# PMP20873E1_Control.net
KiCad netlist of a schematic drawn in Altium Designer
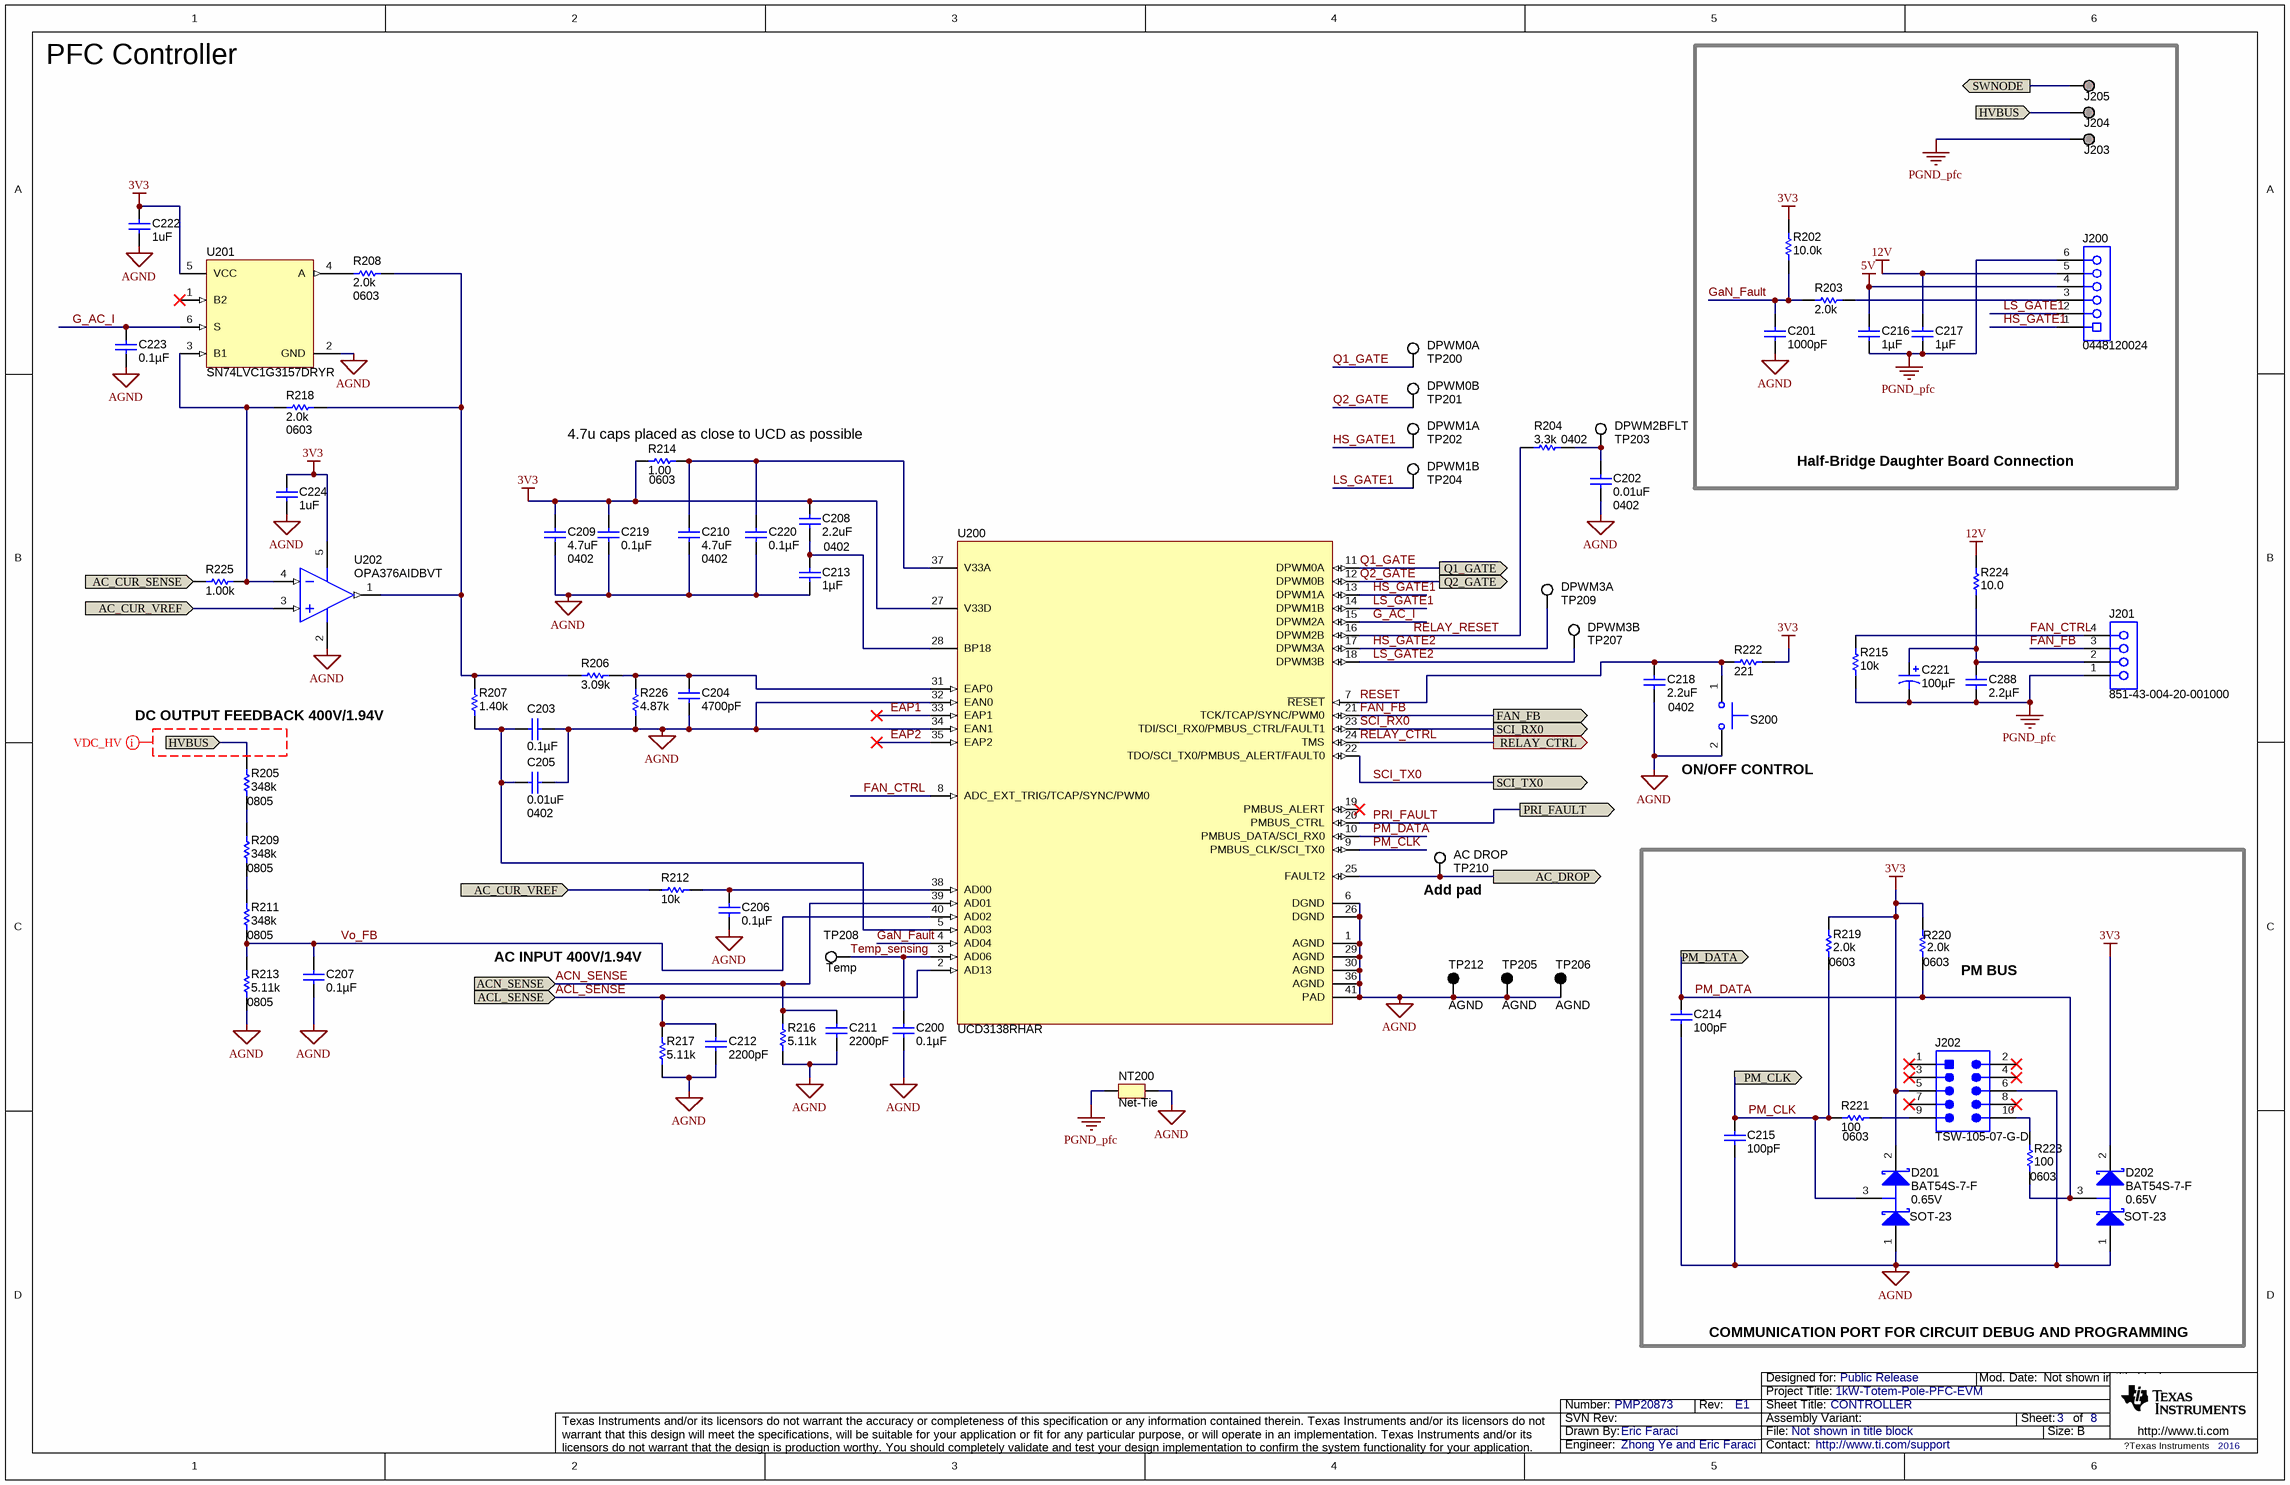
[diagram p0: PMP20873E1_Control.SchDoc]

(export (version "E")
  (design (tool "Eeschema 10.0.6"))
  (components
    (comp (ref "C200")
      (value "GRM155R60J104KA01D")
      (footprint "0402")
      (description "CAP, CERM, 0.1uF, 6.3V, +/-10%, X5R, 0402")
      (fields
        (field (name "VALUEDISPLAYED") "0.1µF")
        (field (name "MANUFACTURER") "MuRata")
        (field (name "PUBLISHER") "Texas Instruments")
      )
      (libsource (lib "Capacitor_Ceramic") (part "GRM155R60J104KA01D"))
    )
    (comp (ref "C201")
      (value "GRM155R61A102KA01D")
      (footprint "0402")
      (description "CAP, CERM, 1000pF, 10V, +/-10%, X5R, 0402")
      (fields
        (field (name "VALUEDISPLAYED") "1000pF")
        (field (name "MANUFACTURER") "MuRata")
        (field (name "PUBLISHER") "Texas Instruments")
      )
      (libsource (lib "Capacitor_Ceramic") (part "GRM155R61A102KA01D"))
    )
    (comp (ref "C202")
      (value "GRM155R70J103KA01D")
      (footprint "0402")
      (description "CAP, CERM, 0.01uF, 6.3V, +/-10%, X7R, 0402")
      (fields
        (field (name "VALUEDISPLAYED") "0.01uF")
        (field (name "MANUFACTURER") "MuRata")
        (field (name "PACKAGEREFERENCE") "0402")
        (field (name "PUBLISHER") "Texas Instruments")
      )
      (libsource (lib "Capacitor_Ceramic") (part "GRM155R70J103KA01D"))
    )
    (comp (ref "C203")
      (value "GRM155R60J104KA01D")
      (footprint "0402")
      (description "CAP, CERM, 0.1uF, 6.3V, +/-10%, X5R, 0402")
      (fields
        (field (name "VALUEDISPLAYED") "0.1µF")
        (field (name "MANUFACTURER") "MuRata")
        (field (name "PUBLISHER") "Texas Instruments")
      )
      (libsource (lib "Capacitor_Ceramic") (part "GRM155R60J104KA01D"))
    )
    (comp (ref "C204")
      (value "GRM155R60J472KA01D")
      (footprint "0402")
      (description "CAP, CERM, 4700pF, 6.3V, +/-10%, X5R, 0402")
      (fields
        (field (name "VALUEDISPLAYED") "4700pF")
        (field (name "MANUFACTURER") "MuRata")
        (field (name "PUBLISHER") "Texas Instruments")
      )
      (libsource (lib "Capacitor_Ceramic") (part "GRM155R60J472KA01D"))
    )
    (comp (ref "C205")
      (value "GRM155R70J103KA01D")
      (footprint "0402")
      (description "CAP, CERM, 0.01uF, 6.3V, +/-10%, X7R, 0402")
      (fields
        (field (name "VALUEDISPLAYED") "0.01uF")
        (field (name "MANUFACTURER") "MuRata")
        (field (name "PACKAGEREFERENCE") "0402")
        (field (name "PUBLISHER") "Texas Instruments")
      )
      (libsource (lib "Capacitor_Ceramic") (part "GRM155R70J103KA01D"))
    )
    (comp (ref "C206")
      (value "GRM155R60J104KA01D")
      (footprint "0402")
      (description "CAP, CERM, 0.1uF, 6.3V, +/-10%, X5R, 0402")
      (fields
        (field (name "VALUEDISPLAYED") "0.1µF")
        (field (name "MANUFACTURER") "MuRata")
        (field (name "PUBLISHER") "Texas Instruments")
      )
      (libsource (lib "Capacitor_Ceramic") (part "GRM155R60J104KA01D"))
    )
    (comp (ref "C207")
      (value "GCM188R71H104KA57D")
      (footprint "0603")
      (description "CAP, CERM, 0.1 µF, 50 V, +/- 10%, X7R, 0603")
      (fields
        (field (name "VALUEDISPLAYED") "0.1µF")
        (field (name "MANUFACTURER") "MuRata")
        (field (name "PUBLISHER") "Texas Instruments")
      )
      (libsource (lib "Capacitor_Ceramic") (part "GCM188R71H104KA57D"))
    )
    (comp (ref "C208")
      (value "C1005X5R1A225K050BC")
      (footprint "0402")
      (description "CAP, CERM, 2.2uF, 10V, +/-10%, X5R, 0402")
      (fields
        (field (name "VALUEDISPLAYED") "2.2uF")
        (field (name "MANUFACTURER") "TDK")
        (field (name "PACKAGEREFERENCE") "0402")
        (field (name "PUBLISHER") "Texas Instruments")
      )
      (libsource (lib "Capacitor_Ceramic") (part "C1005X5R1A225K050BC"))
    )
    (comp (ref "C209")
      (value "4.7uF")
      (footprint "0402")
      (description "CAP, CER, 4.7UF, 6.3V, 20%, X5R, 0402")
      (fields
        (field (name "PACKAGEREFERENCE") "0402")
        (field (name "MANUFACTURER") "Samsung Electro-Mechanics America")
        (field (name "PARTNUMBER") "CL05A475MQ5NRNC")
        (field (name "PUBLISHER") "Texas Instruments")
      )
      (libsource (lib "MiscParts") (part "Capacitor"))
    )
    (comp (ref "C210")
      (value "4.7uF")
      (footprint "0402")
      (description "CAP, CER, 4.7UF, 6.3V, 20%, X5R, 0402")
      (fields
        (field (name "PACKAGEREFERENCE") "0402")
        (field (name "MANUFACTURER") "Samsung Electro-Mechanics America")
        (field (name "PARTNUMBER") "CL05A475MQ5NRNC")
        (field (name "PUBLISHER") "Texas Instruments")
      )
      (libsource (lib "MiscParts") (part "Capacitor"))
    )
    (comp (ref "C211")
      (value "C1608X7R1H222K")
      (footprint "0603")
      (description "CAP, CERM, 2200 pF, 50 V, +/- 10%, X7R, 0603")
      (fields
        (field (name "VALUEDISPLAYED") "2200pF")
        (field (name "MANUFACTURER") "TDK")
        (field (name "PUBLISHER") "Texas Instruments")
      )
      (libsource (lib "Capacitor_Ceramic") (part "C1608X7R1H222K"))
    )
    (comp (ref "C212")
      (value "C1608X7R1H222K")
      (footprint "0603")
      (description "CAP, CERM, 2200 pF, 50 V, +/- 10%, X7R, 0603")
      (fields
        (field (name "VALUEDISPLAYED") "2200pF")
        (field (name "MANUFACTURER") "TDK")
        (field (name "PUBLISHER") "Texas Instruments")
      )
      (libsource (lib "Capacitor_Ceramic") (part "C1608X7R1H222K"))
    )
    (comp (ref "C213")
      (value "GRM155R61A105KE15D")
      (footprint "0402")
      (description "CAP, CERM, 1uF, 10V, +/-10%, X5R, 0402")
      (fields
        (field (name "VALUEDISPLAYED") "1µF")
        (field (name "MANUFACTURER") "MuRata")
        (field (name "PUBLISHER") "Texas Instruments")
      )
      (libsource (lib "Capacitor_Ceramic") (part "GRM155R61A105KE15D"))
    )
    (comp (ref "C214")
      (value "GRM1555C1H101JA01D")
      (footprint "0402")
      (description "CAP, CERM, 100pF, 50V, +/-5%, C0G/NP0, 0402")
      (fields
        (field (name "VALUEDISPLAYED") "100pF")
        (field (name "MANUFACTURER") "MuRata")
        (field (name "PUBLISHER") "Texas Instruments")
      )
      (libsource (lib "Capacitor_Ceramic") (part "GRM1555C1H101JA01D"))
    )
    (comp (ref "C215")
      (value "GRM1555C1H101JA01D")
      (footprint "0402")
      (description "CAP, CERM, 100pF, 50V, +/-5%, C0G/NP0, 0402")
      (fields
        (field (name "VALUEDISPLAYED") "100pF")
        (field (name "MANUFACTURER") "MuRata")
        (field (name "PUBLISHER") "Texas Instruments")
      )
      (libsource (lib "Capacitor_Ceramic") (part "GRM1555C1H101JA01D"))
    )
    (comp (ref "C216")
      (value "C1608X7R1E105K080AB")
      (footprint "0603")
      (description "CAP, CERM, 1 µF, 25 V, +/- 10%, X7R, 0603")
      (fields
        (field (name "VALUEDISPLAYED") "1µF")
        (field (name "MANUFACTURER") "TDK")
        (field (name "PUBLISHER") "Texas Instruments")
      )
      (libsource (lib "Capacitor_Ceramic") (part "C1608X7R1E105K080AB"))
    )
    (comp (ref "C217")
      (value "C1608X7R1E105K080AB")
      (footprint "0603")
      (description "CAP, CERM, 1 µF, 25 V, +/- 10%, X7R, 0603")
      (fields
        (field (name "VALUEDISPLAYED") "1µF")
        (field (name "MANUFACTURER") "TDK")
        (field (name "PUBLISHER") "Texas Instruments")
      )
      (libsource (lib "Capacitor_Ceramic") (part "C1608X7R1E105K080AB"))
    )
    (comp (ref "C218")
      (value "C1005X5R1A225K050BC")
      (footprint "0402")
      (description "CAP, CERM, 2.2uF, 10V, +/-10%, X5R, 0402")
      (fields
        (field (name "VALUEDISPLAYED") "2.2uF")
        (field (name "MANUFACTURER") "TDK")
        (field (name "PACKAGEREFERENCE") "0402")
        (field (name "PUBLISHER") "Texas Instruments")
      )
      (libsource (lib "Capacitor_Ceramic") (part "C1005X5R1A225K050BC"))
    )
    (comp (ref "C219")
      (value "GRM155R60J104KA01D")
      (footprint "0402")
      (description "CAP, CERM, 0.1uF, 6.3V, +/-10%, X5R, 0402")
      (fields
        (field (name "VALUEDISPLAYED") "0.1µF")
        (field (name "MANUFACTURER") "MuRata")
        (field (name "PUBLISHER") "Texas Instruments")
      )
      (libsource (lib "Capacitor_Ceramic") (part "GRM155R60J104KA01D"))
    )
    (comp (ref "C220")
      (value "GRM155R60J104KA01D")
      (footprint "0402")
      (description "CAP, CERM, 0.1uF, 6.3V, +/-10%, X5R, 0402")
      (fields
        (field (name "VALUEDISPLAYED") "0.1µF")
        (field (name "MANUFACTURER") "MuRata")
        (field (name "PUBLISHER") "Texas Instruments")
      )
      (libsource (lib "Capacitor_Ceramic") (part "GRM155R60J104KA01D"))
    )
    (comp (ref "C221")
      (value "T495X107K016ATE100")
      (footprint "7343-43")
      (description "CAP, TA, 100 µF, 16 V, +/- 10%, 0.1 ohm, SMD")
      (fields
        (field (name "VALUEDISPLAYED") "100µF")
        (field (name "MANUFACTURER") "Kemet")
        (field (name "PUBLISHER") "Texas Instruments")
      )
      (libsource (lib "Capacitor_Tantalum") (part "T495X107K016ATE100"))
    )
    (comp (ref "C222")
      (value "C1608X7R1E105K080AB")
      (footprint "0603")
      (description "CAP, CERM, 1uF, 25V, +/-10%, X7R, 0603")
      (fields
        (field (name "VALUEDISPLAYED") "1uF")
        (field (name "MANUFACTURER") "TDK")
        (field (name "PUBLISHER") "Texas Instruments")
      )
      (libsource (lib "Capacitor_Ceramic") (part "C1608X7R1E105K080AB"))
    )
    (comp (ref "C223")
      (value "GCM188R71H104KA57D")
      (footprint "0603")
      (description "CAP, CERM, 0.1 µF, 50 V, +/- 10%, X7R, 0603")
      (fields
        (field (name "VALUEDISPLAYED") "0.1µF")
        (field (name "MANUFACTURER") "MuRata")
        (field (name "PUBLISHER") "Texas Instruments")
      )
      (libsource (lib "Capacitor_Ceramic") (part "GCM188R71H104KA57D"))
    )
    (comp (ref "C224")
      (value "C1608X7R1E105K080AB")
      (footprint "0603")
      (description "CAP, CERM, 1uF, 25V, +/-10%, X7R, 0603")
      (fields
        (field (name "VALUEDISPLAYED") "1uF")
        (field (name "MANUFACTURER") "TDK")
        (field (name "PUBLISHER") "Texas Instruments")
      )
      (libsource (lib "Capacitor_Ceramic") (part "C1608X7R1E105K080AB"))
    )
    (comp (ref "C288")
      (value "12063D225KAT2A")
      (footprint "1206")
      (description "CAP, CERM, 2.2 µF, 25 V, +/- 10%, X5R, 1206")
      (fields
        (field (name "VALUEDISPLAYED") "2.2µF")
        (field (name "MANUFACTURER") "AVX")
        (field (name "PUBLISHER") "Texas Instruments")
      )
      (libsource (lib "Capacitor_Ceramic") (part "12063D225KAT2A"))
    )
    (comp (ref "D201")
      (value "BAT54S-7-F")
      (footprint "SOT-23")
      (description "Diode, Schottky, 30V, 0.2A, SOT-23")
      (fields
        (field (name "MANUFACTURER") "Diodes Inc.")
        (field (name "ALTIUM_VALUE") "0.65V")
        (field (name "PACKAGEREFERENCE") "SOT-23")
        (field (name "PUBLISHER") "Texas Instruments")
      )
      (libsource (lib "Diode") (part "BAT54S-7-F"))
    )
    (comp (ref "D202")
      (value "BAT54S-7-F")
      (footprint "SOT-23")
      (description "Diode, Schottky, 30V, 0.2A, SOT-23")
      (fields
        (field (name "MANUFACTURER") "Diodes Inc.")
        (field (name "ALTIUM_VALUE") "0.65V")
        (field (name "PACKAGEREFERENCE") "SOT-23")
        (field (name "PUBLISHER") "Texas Instruments")
      )
      (libsource (lib "Diode") (part "BAT54S-7-F"))
    )
    (comp (ref "J200")
      (value "0448120024")
      (footprint "Molex_0448120024")
      (description "Receptacle, 2.54mm, 6x1, Gold, TH")
      (fields
        (field (name "MANUFACTURER") "Molex")
        (field (name "SYMBOLCREATOR") "a0411947")
        (field (name "PUBLISHER") "Texas Instruments")
      )
      (libsource (lib "Connectors_Molex") (part "0448120024"))
    )
    (comp (ref "J201")
      (value "851-43-004-20-001000")
      (footprint "CONN_851-43-004-20-001000")
      (description "SOCKET .050\" GRID SIP 4 POS R/A, TH")
      (fields
        (field (name "MANUFACTURER") "Mill-Max")
        (field (name "SYMBOLCREATOR") "a0411947")
        (field (name "PUBLISHER") "Texas Instruments")
      )
      (libsource (lib "Connectors") (part "851-43-004-20-001000"))
    )
    (comp (ref "J202")
      (value "TSW-105-07-G-D")
      (footprint "TSW-105-07-G-D")
      (description "Header, 100mil, 5x2, Gold, TH")
      (fields
        (field (name "MANUFACTURER") "Samtec")
        (field (name "SYMBOLCREATOR") "a0412235")
        (field (name "PUBLISHER") "Texas Instruments")
      )
      (libsource (lib "Connectors_Samtec") (part "TSW-105-07-G-D"))
    )
    (comp (ref "J203")
      (value "Suggest using a net name here")
      (footprint "Mill-Max_0312-0-15-15-34-27-10-0")
      (description "Pin Receptacle, .032-.046\" .075\" Dia, Gold, TH")
      (fields
        (field (name "PARTNUMBER") "0312-0-15-15-34-27-10-0")
        (field (name "MANUFACTURER") "Mill-Max")
        (field (name "PUBLISHER") "Texas Instruments")
      )
      (libsource (lib "Connectors_Mill_Max") (part "0312-0-15-15-34-27-10-0"))
    )
    (comp (ref "J204")
      (value "Suggest using a net name here")
      (footprint "Mill-Max_0312-0-15-15-34-27-10-0")
      (description "Pin Receptacle, .032-.046\" .075\" Dia, Gold, TH")
      (fields
        (field (name "PARTNUMBER") "0312-0-15-15-34-27-10-0")
        (field (name "MANUFACTURER") "Mill-Max")
        (field (name "PUBLISHER") "Texas Instruments")
      )
      (libsource (lib "Connectors_Mill_Max") (part "0312-0-15-15-34-27-10-0"))
    )
    (comp (ref "J205")
      (value "Suggest using a net name here")
      (footprint "Mill-Max_0312-0-15-15-34-27-10-0")
      (description "Pin Receptacle, .032-.046\" .075\" Dia, Gold, TH")
      (fields
        (field (name "PARTNUMBER") "0312-0-15-15-34-27-10-0")
        (field (name "MANUFACTURER") "Mill-Max")
        (field (name "PUBLISHER") "Texas Instruments")
      )
      (libsource (lib "Connectors_Mill_Max") (part "0312-0-15-15-34-27-10-0"))
    )
    (comp (ref "NT200")
      (value "Net-Tie")
      (footprint "Net-Tie_50milWide_30milLong")
      (description "Single point connection between nets.")
      (fields (field (name "SYMBOLCREATOR") "codlsc") (field (name "PUBLISHER") "Texas Instruments"))
      (libsource (lib "MiscParts") (part "Net-Tie"))
    )
    (comp (ref "R202")
      (value "ERJ-2RKF1002X")
      (footprint "0402")
      (description "RES, 10.0 k, 1%, 0.1 W, 0402")
      (fields
        (field (name "VALUEDISPLAYED") "10.0k")
        (field (name "MANUFACTURER") "Panasonic")
        (field (name "PUBLISHER") "Texas Instruments")
      )
      (libsource (lib "Resistor_0402") (part "ERJ-2RKF1002X"))
    )
    (comp (ref "R203")
      (value "2.0k")
      (footprint "0402")
      (description "RES, 2.0k ohm, 5%, 0.063W, 0402")
      (fields
        (field (name "PARTNUMBER") "CRCW04022K00JNED")
        (field (name "MANUFACTURER") "Vishay-Dale")
        (field (name "PUBLISHER") "Texas Instruments")
      )
      (libsource (lib "Resistor_0402") (part "CRCW04022K00JNED"))
    )
    (comp (ref "R204")
      (value "3.3k")
      (footprint "0402")
      (description "RES, 3.3k ohm, 5%, 0.063W, 0402")
      (fields
        (field (name "PARTNUMBER") "CRCW04023K30JNED")
        (field (name "MANUFACTURER") "Vishay-Dale")
        (field (name "PACKAGEREFERENCE") "0402")
        (field (name "PUBLISHER") "Texas Instruments")
      )
      (libsource (lib "Resistor_0402") (part "CRCW04023K30JNED"))
    )
    (comp (ref "R205")
      (value "348k")
      (footprint "0805_HV")
      (description "RES, 348k ohm, 0.1%, 0.125W, 0805")
      (fields
        (field (name "PARTNUMBER") "RT0805BRD07348KL")
        (field (name "MANUFACTURER") "Yageo America")
        (field (name "PACKAGEREFERENCE") "0805")
        (field (name "PUBLISHER") "Texas Instruments")
      )
      (libsource (lib "Resistor_0805") (part "RT0805BRD07348KL"))
    )
    (comp (ref "R206")
      (value "ERA-2AEB3091X")
      (footprint "0402")
      (description "RES, 3.09 k, 0.1%, 0.062 W, AEC-Q200 Grade 0, 0402")
      (fields
        (field (name "VALUEDISPLAYED") "3.09k")
        (field (name "MANUFACTURER") "Panasonic")
        (field (name "PUBLISHER") "Texas Instruments")
      )
      (libsource (lib "Resistor_0402") (part "ERA-2AEB3091X"))
    )
    (comp (ref "R207")
      (value "1.40k")
      (footprint "0402")
      (description "RES, 1.40k ohm, 1%, 0.063W, 0402")
      (fields
        (field (name "PARTNUMBER") "CRCW04021K40FKED")
        (field (name "MANUFACTURER") "Vishay-Dale")
        (field (name "PUBLISHER") "Texas Instruments")
      )
      (libsource (lib "Resistor_0402") (part "CRCW04021K40FKED"))
    )
    (comp (ref "R208")
      (value "2.0k")
      (footprint "0603")
      (description "RES, 2.0k ohm, 5%, 0.1W, 0603")
      (fields
        (field (name "PARTNUMBER") "CRCW06032K00JNEA")
        (field (name "MANUFACTURER") "Vishay-Dale")
        (field (name "PACKAGEREFERENCE") "0603")
        (field (name "PUBLISHER") "Texas Instruments")
      )
      (libsource (lib "Resistor_0603") (part "CRCW06032K00JNEA"))
    )
    (comp (ref "R209")
      (value "348k")
      (footprint "0805_HV")
      (description "RES, 348k ohm, 0.1%, 0.125W, 0805")
      (fields
        (field (name "PARTNUMBER") "RT0805BRD07348KL")
        (field (name "MANUFACTURER") "Yageo America")
        (field (name "PACKAGEREFERENCE") "0805")
        (field (name "PUBLISHER") "Texas Instruments")
      )
      (libsource (lib "Resistor_0805") (part "RT0805BRD07348KL"))
    )
    (comp (ref "R211")
      (value "348k")
      (footprint "0805_HV")
      (description "RES, 348k ohm, 0.1%, 0.125W, 0805")
      (fields
        (field (name "PARTNUMBER") "RT0805BRD07348KL")
        (field (name "MANUFACTURER") "Yageo America")
        (field (name "PACKAGEREFERENCE") "0805")
        (field (name "PUBLISHER") "Texas Instruments")
      )
      (libsource (lib "Resistor_0805") (part "RT0805BRD07348KL"))
    )
    (comp (ref "R212")
      (value "10k")
      (footprint "0402")
      (description "RES, 10k ohm, 5%, 0.063W, 0402")
      (fields
        (field (name "PARTNUMBER") "CRCW040210K0JNED")
        (field (name "MANUFACTURER") "Vishay-Dale")
        (field (name "PUBLISHER") "Texas Instruments")
      )
      (libsource (lib "Resistor_0402") (part "CRCW040210K0JNED"))
    )
    (comp (ref "R213")
      (value "5.11k")
      (footprint "0805_HV")
      (description "RES, 5.11k ohm, 0.1%, 0.125W, 0805")
      (fields
        (field (name "PARTNUMBER") "RT0805BRD075K11L")
        (field (name "MANUFACTURER") "Yageo America")
        (field (name "PACKAGEREFERENCE") "0805")
        (field (name "PUBLISHER") "Texas Instruments")
      )
      (libsource (lib "Resistor_0805") (part "RT0805BRD075K11L"))
    )
    (comp (ref "R214")
      (value "1.00")
      (footprint "0603")
      (description "RES, 1.00 ohm, 1%, 0.1W, 0603")
      (fields
        (field (name "PARTNUMBER") "CRCW06031R00FKEA")
        (field (name "MANUFACTURER") "Vishay-Dale")
        (field (name "PACKAGEREFERENCE") "0603")
        (field (name "PUBLISHER") "Texas Instruments")
      )
      (libsource (lib "Resistor_0603") (part "CRCW06031R00FKEA"))
    )
    (comp (ref "R215")
      (value "10k")
      (footprint "0402")
      (description "RES, 10k ohm, 5%, 0.063W, 0402")
      (fields
        (field (name "PARTNUMBER") "CRCW040210K0JNED")
        (field (name "MANUFACTURER") "Vishay-Dale")
        (field (name "PUBLISHER") "Texas Instruments")
      )
      (libsource (lib "Resistor_0402") (part "CRCW040210K0JNED"))
    )
    (comp (ref "R216")
      (value "RT0603BRD075K11L")
      (footprint "0603")
      (description "RES, 5.11 k, 0.1%, 0.1 W, 0603")
      (fields
        (field (name "VALUEDISPLAYED") "5.11k")
        (field (name "MANUFACTURER") "Yageo America")
        (field (name "PUBLISHER") "Texas Instruments")
      )
      (libsource (lib "Resistor_0603") (part "RT0603BRD075K11L"))
    )
    (comp (ref "R217")
      (value "RT0603BRD075K11L")
      (footprint "0603")
      (description "RES, 5.11 k, 0.1%, 0.1 W, 0603")
      (fields
        (field (name "VALUEDISPLAYED") "5.11k")
        (field (name "MANUFACTURER") "Yageo America")
        (field (name "PUBLISHER") "Texas Instruments")
      )
      (libsource (lib "Resistor_0603") (part "RT0603BRD075K11L"))
    )
    (comp (ref "R218")
      (value "2.0k")
      (footprint "0603")
      (description "RES, 2.0k ohm, 5%, 0.1W, 0603")
      (fields
        (field (name "PARTNUMBER") "CRCW06032K00JNEA")
        (field (name "MANUFACTURER") "Vishay-Dale")
        (field (name "PACKAGEREFERENCE") "0603")
        (field (name "PUBLISHER") "Texas Instruments")
      )
      (libsource (lib "Resistor_0603") (part "CRCW06032K00JNEA"))
    )
    (comp (ref "R219")
      (value "2.0k")
      (footprint "0603")
      (description "RES, 2.0k ohm, 5%, 0.1W, 0603")
      (fields
        (field (name "PARTNUMBER") "CRCW06032K00JNEA")
        (field (name "MANUFACTURER") "Vishay-Dale")
        (field (name "PACKAGEREFERENCE") "0603")
        (field (name "PUBLISHER") "Texas Instruments")
      )
      (libsource (lib "Resistor_0603") (part "CRCW06032K00JNEA"))
    )
    (comp (ref "R220")
      (value "2.0k")
      (footprint "0603")
      (description "RES, 2.0k ohm, 5%, 0.1W, 0603")
      (fields
        (field (name "PARTNUMBER") "CRCW06032K00JNEA")
        (field (name "MANUFACTURER") "Vishay-Dale")
        (field (name "PACKAGEREFERENCE") "0603")
        (field (name "PUBLISHER") "Texas Instruments")
      )
      (libsource (lib "Resistor_0603") (part "CRCW06032K00JNEA"))
    )
    (comp (ref "R221")
      (value "100")
      (footprint "0603")
      (description "RES, 100 ohm, 5%, 0.1W, 0603")
      (fields
        (field (name "PARTNUMBER") "CRCW0603100RJNEA")
        (field (name "MANUFACTURER") "Vishay-Dale")
        (field (name "PACKAGEREFERENCE") "0603")
        (field (name "PUBLISHER") "Texas Instruments")
      )
      (libsource (lib "Resistor_0603") (part "CRCW0603100RJNEA"))
    )
    (comp (ref "R222")
      (value "CRCW0402221RFKED")
      (footprint "0402")
      (description "RES, 221, 1%, 0.063 W, 0402")
      (fields
        (field (name "VALUEDISPLAYED") "221")
        (field (name "MANUFACTURER") "Vishay-Dale")
        (field (name "PUBLISHER") "Texas Instruments")
      )
      (libsource (lib "Resistor_0402") (part "CRCW0402221RFKED"))
    )
    (comp (ref "R223")
      (value "100")
      (footprint "0603")
      (description "RES, 100 ohm, 5%, 0.1W, 0603")
      (fields
        (field (name "PARTNUMBER") "CRCW0603100RJNEA")
        (field (name "MANUFACTURER") "Vishay-Dale")
        (field (name "PACKAGEREFERENCE") "0603")
        (field (name "PUBLISHER") "Texas Instruments")
      )
      (libsource (lib "Resistor_0603") (part "CRCW0603100RJNEA"))
    )
    (comp (ref "R224")
      (value "ERJ-8ENF10R0V")
      (footprint "1206")
      (description "RES, 10.0, 1%, 0.25 W, 1206")
      (fields
        (field (name "VALUEDISPLAYED") "10.0")
        (field (name "MANUFACTURER") "Panasonic")
        (field (name "PUBLISHER") "Texas Instruments")
      )
      (libsource (lib "Resistor_1206") (part "ERJ-8ENF10R0V"))
    )
    (comp (ref "R225")
      (value "RC0603FR-071KL")
      (footprint "0603")
      (description "RES, 1.00 k, 1%, 0.1 W, 0603")
      (fields
        (field (name "VALUEDISPLAYED") "1.00k")
        (field (name "MANUFACTURER") "Yageo America")
        (field (name "PUBLISHER") "Texas Instruments")
      )
      (libsource (lib "Resistor_0603") (part "RC0603FR-071KL"))
    )
    (comp (ref "R226")
      (value "ERA-2AEB4871X")
      (footprint "0402")
      (description "RES, 4.87 k, 0.1%, 0.062 W, AEC-Q200 Grade 0, 0402")
      (fields
        (field (name "VALUEDISPLAYED") "4.87k")
        (field (name "MANUFACTURER") "Panasonic")
        (field (name "PUBLISHER") "Texas Instruments")
      )
      (libsource (lib "Resistor_0402") (part "ERA-2AEB4871X"))
    )
    (comp (ref "S200")
      (value "SKRKAEE010")
      (footprint "SW_SKRKAEE010")
      (description "Switch, Push Button, SMD")
      (fields
        (field (name "MANUFACTURER") "Alps")
        (field (name "SYMBOLCREATOR") "a0412235")
        (field (name "PUBLISHER") "Texas Instruments")
      )
      (libsource (lib "Switches") (part "SKRKAEE010"))
    )
    (comp (ref "TP200")
      (value "DPWM0A")
      (footprint "Keystone5002")
      (description "Test Point, Miniature, White, TH")
      (fields
        (field (name "PARTNUMBER") "5002")
        (field (name "MANUFACTURER") "Keystone")
        (field (name "PUBLISHER") "Texas Instruments")
      )
      (libsource (lib "Connectors_Keystone") (part "5002"))
    )
    (comp (ref "TP201")
      (value "DPWM0B")
      (footprint "Keystone5002")
      (description "Test Point, Miniature, White, TH")
      (fields
        (field (name "PARTNUMBER") "5002")
        (field (name "MANUFACTURER") "Keystone")
        (field (name "PUBLISHER") "Texas Instruments")
      )
      (libsource (lib "Connectors_Keystone") (part "5002"))
    )
    (comp (ref "TP202")
      (value "DPWM1A")
      (footprint "Keystone5002")
      (description "Test Point, Miniature, White, TH")
      (fields
        (field (name "PARTNUMBER") "5002")
        (field (name "MANUFACTURER") "Keystone")
        (field (name "PUBLISHER") "Texas Instruments")
      )
      (libsource (lib "Connectors_Keystone") (part "5002"))
    )
    (comp (ref "TP203")
      (value "DPWM2BFLT")
      (footprint "Keystone5002")
      (description "Test Point, Miniature, White, TH")
      (fields
        (field (name "PARTNUMBER") "5002")
        (field (name "MANUFACTURER") "Keystone")
        (field (name "PUBLISHER") "Texas Instruments")
      )
      (libsource (lib "Connectors_Keystone") (part "5002"))
    )
    (comp (ref "TP204")
      (value "DPWM1B")
      (footprint "Keystone5002")
      (description "Test Point, Miniature, White, TH")
      (fields
        (field (name "PARTNUMBER") "5002")
        (field (name "MANUFACTURER") "Keystone")
        (field (name "PUBLISHER") "Texas Instruments")
      )
      (libsource (lib "Connectors_Keystone") (part "5002"))
    )
    (comp (ref "TP205")
      (value "AGND")
      (footprint "Keystone5001")
      (description "Test Point, Miniature, Black, TH")
      (fields
        (field (name "PARTNUMBER") "5001")
        (field (name "MANUFACTURER") "Keystone")
        (field (name "PUBLISHER") "Texas Instruments")
      )
      (libsource (lib "Connectors") (part "5001"))
    )
    (comp (ref "TP206")
      (value "AGND")
      (footprint "Keystone5001")
      (description "Test Point, Miniature, Black, TH")
      (fields
        (field (name "PARTNUMBER") "5001")
        (field (name "MANUFACTURER") "Keystone")
        (field (name "PUBLISHER") "Texas Instruments")
      )
      (libsource (lib "Connectors") (part "5001"))
    )
    (comp (ref "TP207")
      (value "DPWM3B")
      (footprint "Keystone5002")
      (description "Test Point, Miniature, White, TH")
      (fields
        (field (name "PARTNUMBER") "5002")
        (field (name "MANUFACTURER") "Keystone")
        (field (name "PUBLISHER") "Texas Instruments")
      )
      (libsource (lib "Connectors_Keystone") (part "5002"))
    )
    (comp (ref "TP208")
      (value "Temp")
      (footprint "Keystone5002")
      (description "Test Point, Miniature, White, TH")
      (fields
        (field (name "PARTNUMBER") "5002")
        (field (name "MANUFACTURER") "Keystone")
        (field (name "PUBLISHER") "Texas Instruments")
      )
      (libsource (lib "Connectors_Keystone") (part "5002"))
    )
    (comp (ref "TP209")
      (value "DPWM3A")
      (footprint "Keystone5002")
      (description "Test Point, Miniature, White, TH")
      (fields
        (field (name "PARTNUMBER") "5002")
        (field (name "MANUFACTURER") "Keystone")
        (field (name "PUBLISHER") "Texas Instruments")
      )
      (libsource (lib "Connectors_Keystone") (part "5002"))
    )
    (comp (ref "TP210")
      (value "AC DROP")
      (footprint "Keystone5002")
      (description "Test Point, Miniature, White, TH")
      (fields
        (field (name "PARTNUMBER") "5002")
        (field (name "MANUFACTURER") "Keystone")
        (field (name "PUBLISHER") "Texas Instruments")
      )
      (libsource (lib "Connectors_Keystone") (part "5002"))
    )
    (comp (ref "TP212")
      (value "AGND")
      (footprint "Keystone5001")
      (description "Test Point, Miniature, Black, TH")
      (fields
        (field (name "PARTNUMBER") "5001")
        (field (name "MANUFACTURER") "Keystone")
        (field (name "PUBLISHER") "Texas Instruments")
      )
      (libsource (lib "Connectors") (part "5001"))
    )
    (comp (ref "U200")
      (value "UCD3138RHAR")
      (footprint "RHA0040B")
      (description "Highly Integrated Digital Controller for Isolated Power, RHA0040B")
      (fields
        (field (name "ALTERNATE PARTNUMBER") "UCD3138RHAT")
        (field (name "MANUFACTURER") "Texas Instruments")
        (field (name "SYMBOLCREATOR") "Altium")
        (field (name "PUBLISHER") "Texas Instruments")
      )
      (libsource (lib "TI_Pre_Release") (part "UCD3138RHAR"))
    )
    (comp (ref "U201")
      (value "SN74LVC1G3157DRYR")
      (footprint "DRY0006A")
      (description "SINGLE-POLE DOUBLE-THROW ANALOG SWITCH, DRY0006A")
      (fields
        (field (name "MANUFACTURER") "Texas Instruments")
        (field (name "SYMBOLCREATOR") "a0799628")
        (field (name "PUBLISHER") "Texas Instruments")
      )
      (libsource (lib "TI_Pre_Release") (part "SN74LVC1G3157DRYR"))
    )
    (comp (ref "U202")
      (value "OPA376AIDBVT")
      (footprint "DBV0005A_N")
      (fields
        (field (name "MANUFACTURER") "Texas Instruments")
        (field (name "ALTERNATE PARTNUMBER") "Equivalent")
      )
      (libsource (lib "TI Amplifiers and Linear Operational Amplifier Precision Amplifier Part One") (part "OPA376AIDBVT"))
    )
  )
  (nets
    (net (code "1") (name "/ACL_SENSE") (class "Default")
      (node (ref "C212") (pin "1") (pinfunction "1_1") (pintype "passive"))
      (node (ref "R217") (pin "2") (pinfunction "2_2") (pintype "passive"))
      (node (ref "U200") (pin "2") (pinfunction "AD13_2") (pintype "input"))
    )
    (net (code "2") (name "/ACN_SENSE") (class "Default")
      (node (ref "C211") (pin "1") (pinfunction "1_1") (pintype "passive"))
      (node (ref "R216") (pin "2") (pinfunction "2_2") (pintype "passive"))
      (node (ref "U200") (pin "39") (pinfunction "AD01_39") (pintype "input"))
    )
    (net (code "3") (name "/AC_CUR_SENSE") (class "Default")
      (node (ref "R225") (pin "1") (pinfunction "1_1") (pintype "passive"))
    )
    (net (code "4") (name "/AC_CUR_VREF") (class "Default")
      (node (ref "R212") (pin "2") (pinfunction "2_2") (pintype "passive"))
      (node (ref "U202") (pin "3") (pinfunction "IN+_3") (pintype "input"))
    )
    (net (code "5") (name "/AC_DROP") (class "Default")
      (node (ref "TP210") (pin "1") (pintype "passive"))
      (node (ref "U200") (pin "25") (pinfunction "FAULT2_25") (pintype "bidirectional"))
    )
    (net (code "6") (name "/EAP1") (class "Default")
      (node (ref "U200") (pin "33") (pinfunction "EAP1_33") (pintype "input+no_connect"))
    )
    (net (code "7") (name "/EAP2") (class "Default")
      (node (ref "U200") (pin "35") (pinfunction "EAP2_35") (pintype "input+no_connect"))
    )
    (net (code "8") (name "/FAN_CTRL") (class "Default")
      (node (ref "J201") (pin "4") (pinfunction "4_4") (pintype "passive"))
      (node (ref "R215") (pin "2") (pinfunction "2_2") (pintype "passive"))
      (node (ref "U200") (pin "8") (pinfunction "ADC_EXT_TRIG/TCAP/SYNC/PWM0_8") (pintype "input"))
    )
    (net (code "9") (name "/FAN_FB") (class "Default")
      (node (ref "J201") (pin "3") (pinfunction "3_3") (pintype "passive"))
      (node (ref "U200") (pin "21") (pinfunction "TCK/TCAP/SYNC/PWM0_21") (pintype "bidirectional"))
    )
    (net (code "10") (name "/G_AC_I") (class "Default")
      (node (ref "C223") (pin "1") (pinfunction "1_1") (pintype "passive"))
      (node (ref "U200") (pin "15") (pinfunction "DPWM2A_15") (pintype "bidirectional"))
      (node (ref "U201") (pin "6") (pinfunction "S_6") (pintype "input"))
    )
    (net (code "11") (name "/GaN_Fault") (class "Default")
      (node (ref "C201") (pin "1") (pinfunction "1_1") (pintype "passive"))
      (node (ref "R202") (pin "1") (pinfunction "1_1") (pintype "passive"))
      (node (ref "R203") (pin "1") (pinfunction "1_1") (pintype "passive"))
      (node (ref "U200") (pin "4") (pinfunction "AD04_4") (pintype "input"))
    )
    (net (code "12") (name "/HS_GATE1") (class "Default")
      (node (ref "J200") (pin "1") (pinfunction "1_1") (pintype "passive"))
      (node (ref "TP202") (pin "1") (pintype "passive"))
      (node (ref "U200") (pin "13") (pinfunction "DPWM1A_13") (pintype "bidirectional"))
    )
    (net (code "13") (name "/HS_GATE2") (class "Default")
      (node (ref "TP209") (pin "1") (pintype "passive"))
      (node (ref "U200") (pin "17") (pinfunction "DPWM3A_17") (pintype "bidirectional"))
    )
    (net (code "14") (name "/HVBUS") (class "Default")
      (node (ref "J204") (pin "1") (pintype "passive"))
      (node (ref "R205") (pin "2") (pinfunction "2_2") (pintype "passive"))
    )
    (net (code "15") (name "/LS_GATE1") (class "Default")
      (node (ref "J200") (pin "2") (pinfunction "2_2") (pintype "passive"))
      (node (ref "TP204") (pin "1") (pintype "passive"))
      (node (ref "U200") (pin "14") (pinfunction "DPWM1B_14") (pintype "bidirectional"))
    )
    (net (code "16") (name "/LS_GATE2") (class "Default")
      (node (ref "TP207") (pin "1") (pintype "passive"))
      (node (ref "U200") (pin "18") (pinfunction "DPWM3B_18") (pintype "bidirectional"))
    )
    (net (code "17") (name "/PM_CLK") (class "Default")
      (node (ref "C215") (pin "1") (pinfunction "1_1") (pintype "passive"))
      (node (ref "D201") (pin "3") (pinfunction "C_3") (pintype "passive"))
      (node (ref "R219") (pin "1") (pinfunction "1_1") (pintype "passive"))
      (node (ref "R221") (pin "1") (pinfunction "1_1") (pintype "passive"))
      (node (ref "U200") (pin "9") (pinfunction "PMBUS_CLK/SCI_TX0_9") (pintype "bidirectional"))
    )
    (net (code "18") (name "/PM_DATA") (class "Default")
      (node (ref "C214") (pin "1") (pinfunction "1_1") (pintype "passive"))
      (node (ref "D202") (pin "3") (pinfunction "C_3") (pintype "passive"))
      (node (ref "R220") (pin "1") (pinfunction "1_1") (pintype "passive"))
      (node (ref "R223") (pin "1") (pinfunction "1_1") (pintype "passive"))
      (node (ref "U200") (pin "10") (pinfunction "PMBUS_DATA/SCI_RX0_10") (pintype "bidirectional"))
    )
    (net (code "19") (name "/PRI_FAULT") (class "Default")
      (node (ref "U200") (pin "20") (pinfunction "PMBUS_CTRL_20") (pintype "bidirectional"))
    )
    (net (code "20") (name "/Q1_GATE") (class "Default")
      (node (ref "TP200") (pin "1") (pintype "passive"))
      (node (ref "U200") (pin "11") (pinfunction "DPWM0A_11") (pintype "bidirectional"))
    )
    (net (code "21") (name "/Q2_GATE") (class "Default")
      (node (ref "TP201") (pin "1") (pintype "passive"))
      (node (ref "U200") (pin "12") (pinfunction "DPWM0B_12") (pintype "bidirectional"))
    )
    (net (code "22") (name "/RELAY_CTRL") (class "Default")
      (node (ref "U200") (pin "24") (pinfunction "TMS_24") (pintype "bidirectional"))
    )
    (net (code "23") (name "/RELAY_RESET") (class "Default")
      (node (ref "R204") (pin "1") (pinfunction "1_1") (pintype "passive"))
      (node (ref "U200") (pin "16") (pinfunction "DPWM2B_16") (pintype "bidirectional"))
    )
    (net (code "24") (name "/RESET") (class "Default")
      (node (ref "C218") (pin "1") (pinfunction "1_1") (pintype "passive"))
      (node (ref "R222") (pin "1") (pinfunction "1_1") (pintype "passive"))
      (node (ref "S200") (pin "1") (pinfunction "1_1") (pintype "passive"))
      (node (ref "U200") (pin "7") (pinfunction "RESET_7") (pintype "input"))
    )
    (net (code "25") (name "/SCI_RX0") (class "Default")
      (node (ref "U200") (pin "23") (pinfunction "TDI/SCI_RX0/PMBUS_CTRL/FAULT1_23") (pintype "bidirectional"))
    )
    (net (code "26") (name "/SCI_TX0") (class "Default")
      (node (ref "U200") (pin "22") (pinfunction "TDO/SCI_TX0/PMBUS_ALERT/FAULT0_22") (pintype "bidirectional"))
    )
    (net (code "27") (name "/SWNODE") (class "Default") (node (ref "J205") (pin "1") (pintype "passive")))
    (net (code "28") (name "/Temp_sensing") (class "Default")
      (node (ref "C200") (pin "2") (pinfunction "2_2") (pintype "passive"))
      (node (ref "TP208") (pin "1") (pintype "passive"))
      (node (ref "U200") (pin "3") (pinfunction "AD06_3") (pintype "input"))
    )
    (net (code "29") (name "/Vo_FB") (class "Default")
      (node (ref "C207") (pin "1") (pinfunction "1_1") (pintype "passive"))
      (node (ref "R211") (pin "1") (pinfunction "1_1") (pintype "passive"))
      (node (ref "R213") (pin "2") (pinfunction "2_2") (pintype "passive"))
      (node (ref "U200") (pin "40") (pinfunction "AD02_40") (pintype "input"))
    )
    (net (code "30") (name "3V3") (class "Default")
      (node (ref "C208") (pin "1") (pinfunction "1_1") (pintype "passive"))
      (node (ref "C209") (pin "1") (pinfunction "1_1") (pintype "passive"))
      (node (ref "C219") (pin "1") (pinfunction "1_1") (pintype "passive"))
      (node (ref "C222") (pin "2") (pinfunction "2_2") (pintype "passive"))
      (node (ref "C224") (pin "2") (pinfunction "2_2") (pintype "passive"))
      (node (ref "D201") (pin "2") (pinfunction "K_2") (pintype "passive"))
      (node (ref "D202") (pin "2") (pinfunction "K_2") (pintype "passive"))
      (node (ref "J202") (pin "5") (pinfunction "5_5") (pintype "passive"))
      (node (ref "R202") (pin "2") (pinfunction "2_2") (pintype "passive"))
      (node (ref "R214") (pin "2") (pinfunction "2_2") (pintype "passive"))
      (node (ref "R219") (pin "2") (pinfunction "2_2") (pintype "passive"))
      (node (ref "R220") (pin "2") (pinfunction "2_2") (pintype "passive"))
      (node (ref "R222") (pin "2") (pinfunction "2_2") (pintype "passive"))
      (node (ref "U200") (pin "27") (pinfunction "V33D_27") (pintype "power_in"))
      (node (ref "U201") (pin "5") (pinfunction "VCC_5") (pintype "power_in"))
      (node (ref "U202") (pin "5") (pinfunction "V+_5") (pintype "power_in"))
    )
    (net (code "31") (name "5V") (class "Default")
      (node (ref "C216") (pin "2") (pinfunction "2_2") (pintype "passive"))
      (node (ref "J200") (pin "4") (pinfunction "4_4") (pintype "passive"))
    )
    (net (code "32") (name "12V") (class "Default")
      (node (ref "C217") (pin "2") (pinfunction "2_2") (pintype "passive"))
      (node (ref "J200") (pin "5") (pinfunction "5_5") (pintype "passive"))
      (node (ref "R224") (pin "2") (pinfunction "2_2") (pintype "passive"))
    )
    (net (code "33") (name "AGND") (class "Default")
      (node (ref "C200") (pin "1") (pinfunction "1_1") (pintype "passive"))
      (node (ref "C201") (pin "2") (pinfunction "2_2") (pintype "passive"))
      (node (ref "C202") (pin "1") (pinfunction "1_1") (pintype "passive"))
      (node (ref "C203") (pin "2") (pinfunction "2_2") (pintype "passive"))
      (node (ref "C204") (pin "2") (pinfunction "2_2") (pintype "passive"))
      (node (ref "C205") (pin "2") (pinfunction "2_2") (pintype "passive"))
      (node (ref "C206") (pin "1") (pinfunction "1_1") (pintype "passive"))
      (node (ref "C207") (pin "2") (pinfunction "2_2") (pintype "passive"))
      (node (ref "C209") (pin "2") (pinfunction "2_2") (pintype "passive"))
      (node (ref "C210") (pin "2") (pinfunction "2_2") (pintype "passive"))
      (node (ref "C211") (pin "2") (pinfunction "2_2") (pintype "passive"))
      (node (ref "C212") (pin "2") (pinfunction "2_2") (pintype "passive"))
      (node (ref "C213") (pin "2") (pinfunction "2_2") (pintype "passive"))
      (node (ref "C214") (pin "2") (pinfunction "2_2") (pintype "passive"))
      (node (ref "C215") (pin "2") (pinfunction "2_2") (pintype "passive"))
      (node (ref "C218") (pin "2") (pinfunction "2_2") (pintype "passive"))
      (node (ref "C219") (pin "2") (pinfunction "2_2") (pintype "passive"))
      (node (ref "C220") (pin "2") (pinfunction "2_2") (pintype "passive"))
      (node (ref "C222") (pin "1") (pinfunction "1_1") (pintype "passive"))
      (node (ref "C223") (pin "2") (pinfunction "2_2") (pintype "passive"))
      (node (ref "C224") (pin "1") (pinfunction "1_1") (pintype "passive"))
      (node (ref "D201") (pin "1") (pinfunction "A_1") (pintype "passive"))
      (node (ref "D202") (pin "1") (pinfunction "A_1") (pintype "passive"))
      (node (ref "J202") (pin "6") (pinfunction "6_6") (pintype "passive"))
      (node (ref "NT200") (pin "2") (pinfunction "2_2") (pintype "passive"))
      (node (ref "R213") (pin "1") (pinfunction "1_1") (pintype "passive"))
      (node (ref "R216") (pin "1") (pinfunction "1_1") (pintype "passive"))
      (node (ref "R217") (pin "1") (pinfunction "1_1") (pintype "passive"))
      (node (ref "R226") (pin "1") (pinfunction "1_1") (pintype "passive"))
      (node (ref "S200") (pin "2") (pinfunction "2_2") (pintype "passive"))
      (node (ref "TP205") (pin "1") (pintype "passive"))
      (node (ref "TP206") (pin "1") (pintype "passive"))
      (node (ref "TP212") (pin "1") (pintype "passive"))
      (node (ref "U200") (pin "1") (pinfunction "AGND_1") (pintype "power_in"))
      (node (ref "U200") (pin "26") (pinfunction "DGND_26") (pintype "power_in"))
      (node (ref "U200") (pin "29") (pinfunction "AGND_29") (pintype "power_in"))
      (node (ref "U200") (pin "30") (pinfunction "AGND_30") (pintype "power_in"))
      (node (ref "U200") (pin "32") (pinfunction "EAN0_32") (pintype "input"))
      (node (ref "U200") (pin "34") (pinfunction "EAN1_34") (pintype "input"))
      (node (ref "U200") (pin "36") (pinfunction "AGND_36") (pintype "power_in"))
      (node (ref "U200") (pin "41") (pinfunction "PAD_41") (pintype "power_in"))
      (node (ref "U200") (pin "6") (pinfunction "DGND_6") (pintype "power_in"))
      (node (ref "U201") (pin "2") (pinfunction "GND_2") (pintype "power_in"))
      (node (ref "U202") (pin "2") (pinfunction "V-_2") (pintype "power_in"))
    )
    (net (code "34") (name "Net-(C202-Pad2)") (class "Default")
      (node (ref "C202") (pin "2") (pinfunction "2_2") (pintype "passive"))
      (node (ref "R204") (pin "2") (pinfunction "2_2") (pintype "passive"))
      (node (ref "TP203") (pin "1") (pintype "passive"))
    )
    (net (code "35") (name "Net-(C221-+)") (class "Default")
      (node (ref "C221") (pin "1") (pinfunction "+_1") (pintype "passive"))
      (node (ref "C288") (pin "2") (pinfunction "2_2") (pintype "passive"))
      (node (ref "J201") (pin "2") (pinfunction "2_2") (pintype "passive"))
      (node (ref "R224") (pin "1") (pinfunction "1_1") (pintype "passive"))
    )
    (net (code "36") (name "Net-(J200-Pad3)") (class "Default")
      (node (ref "J200") (pin "3") (pinfunction "3_3") (pintype "passive"))
      (node (ref "R203") (pin "2") (pinfunction "2_2") (pintype "passive"))
    )
    (net (code "37") (name "Net-(J202-Pad9)") (class "Default")
      (node (ref "J202") (pin "9") (pinfunction "9_9") (pintype "passive"))
      (node (ref "R221") (pin "2") (pinfunction "2_2") (pintype "passive"))
    )
    (net (code "38") (name "Net-(J202-Pad10)") (class "Default")
      (node (ref "J202") (pin "10") (pinfunction "10_10") (pintype "passive"))
      (node (ref "R223") (pin "2") (pinfunction "2_2") (pintype "passive"))
    )
    (net (code "39") (name "Net-(R205-Pad1)") (class "Default")
      (node (ref "R205") (pin "1") (pinfunction "1_1") (pintype "passive"))
      (node (ref "R209") (pin "2") (pinfunction "2_2") (pintype "passive"))
    )
    (net (code "40") (name "Net-(R209-Pad1)") (class "Default")
      (node (ref "R209") (pin "1") (pinfunction "1_1") (pintype "passive"))
      (node (ref "R211") (pin "2") (pinfunction "2_2") (pintype "passive"))
    )
    (net (code "41") (name "Net-(U200-AD00)") (class "Default")
      (node (ref "C206") (pin "2") (pinfunction "2_2") (pintype "passive"))
      (node (ref "R212") (pin "1") (pinfunction "1_1") (pintype "passive"))
      (node (ref "U200") (pin "38") (pinfunction "AD00_38") (pintype "input"))
    )
    (net (code "42") (name "Net-(U200-AD03)") (class "Default")
      (node (ref "C203") (pin "1") (pinfunction "1_1") (pintype "passive"))
      (node (ref "C205") (pin "1") (pinfunction "1_1") (pintype "passive"))
      (node (ref "R207") (pin "1") (pinfunction "1_1") (pintype "passive"))
      (node (ref "U200") (pin "5") (pinfunction "AD03_5") (pintype "input"))
    )
    (net (code "43") (name "Net-(U200-BP18)") (class "Default")
      (node (ref "C208") (pin "2") (pinfunction "2_2") (pintype "passive"))
      (node (ref "C213") (pin "1") (pinfunction "1_1") (pintype "passive"))
      (node (ref "U200") (pin "28") (pinfunction "BP18_28") (pintype "power_in"))
    )
    (net (code "44") (name "Net-(U200-EAP0)") (class "Default")
      (node (ref "C204") (pin "1") (pinfunction "1_1") (pintype "passive"))
      (node (ref "R206") (pin "2") (pinfunction "2_2") (pintype "passive"))
      (node (ref "R226") (pin "2") (pinfunction "2_2") (pintype "passive"))
      (node (ref "U200") (pin "31") (pinfunction "EAP0_31") (pintype "input"))
    )
    (net (code "45") (name "Net-(U200-V33A)") (class "Default")
      (node (ref "C210") (pin "1") (pinfunction "1_1") (pintype "passive"))
      (node (ref "C220") (pin "1") (pinfunction "1_1") (pintype "passive"))
      (node (ref "R214") (pin "1") (pinfunction "1_1") (pintype "passive"))
      (node (ref "U200") (pin "37") (pinfunction "V33A_37") (pintype "power_in"))
    )
    (net (code "46") (name "Net-(U201-A)") (class "Default")
      (node (ref "R208") (pin "2") (pinfunction "2_2") (pintype "passive"))
      (node (ref "U201") (pin "4") (pinfunction "A_4") (pintype "output"))
    )
    (net (code "47") (name "Net-(U201-B1)") (class "Default")
      (node (ref "R218") (pin "2") (pinfunction "2_2") (pintype "passive"))
      (node (ref "R225") (pin "2") (pinfunction "2_2") (pintype "passive"))
      (node (ref "U201") (pin "3") (pinfunction "B1_3") (pintype "input"))
      (node (ref "U202") (pin "4") (pinfunction "IN-_4") (pintype "input"))
    )
    (net (code "48") (name "Net-(U202-OUT)") (class "Default")
      (node (ref "R206") (pin "1") (pinfunction "1_1") (pintype "passive"))
      (node (ref "R207") (pin "2") (pinfunction "2_2") (pintype "passive"))
      (node (ref "R208") (pin "1") (pinfunction "1_1") (pintype "passive"))
      (node (ref "R218") (pin "1") (pinfunction "1_1") (pintype "passive"))
      (node (ref "U202") (pin "1") (pinfunction "OUT_1") (pintype "output"))
    )
    (net (code "49") (name "PGND_pfc") (class "Default")
      (node (ref "C216") (pin "1") (pinfunction "1_1") (pintype "passive"))
      (node (ref "C217") (pin "1") (pinfunction "1_1") (pintype "passive"))
      (node (ref "C221") (pin "2") (pinfunction "-_2") (pintype "passive"))
      (node (ref "C288") (pin "1") (pinfunction "1_1") (pintype "passive"))
      (node (ref "J200") (pin "6") (pinfunction "6_6") (pintype "passive"))
      (node (ref "J201") (pin "1") (pinfunction "1_1") (pintype "passive"))
      (node (ref "J203") (pin "1") (pintype "passive"))
      (node (ref "NT200") (pin "1") (pinfunction "1_1") (pintype "passive"))
      (node (ref "R215") (pin "1") (pinfunction "1_1") (pintype "passive"))
    )
    (net (code "50") (name "unconnected-(J202-Pad1)") (class "Default")
      (node (ref "J202") (pin "1") (pinfunction "1_1") (pintype "passive+no_connect"))
    )
    (net (code "51") (name "unconnected-(J202-Pad2)") (class "Default")
      (node (ref "J202") (pin "2") (pinfunction "2_2") (pintype "passive+no_connect"))
    )
    (net (code "52") (name "unconnected-(J202-Pad3)") (class "Default")
      (node (ref "J202") (pin "3") (pinfunction "3_3") (pintype "passive+no_connect"))
    )
    (net (code "53") (name "unconnected-(J202-Pad4)") (class "Default")
      (node (ref "J202") (pin "4") (pinfunction "4_4") (pintype "passive+no_connect"))
    )
    (net (code "54") (name "unconnected-(J202-Pad7)") (class "Default")
      (node (ref "J202") (pin "7") (pinfunction "7_7") (pintype "passive+no_connect"))
    )
    (net (code "55") (name "unconnected-(J202-Pad8)") (class "Default")
      (node (ref "J202") (pin "8") (pinfunction "8_8") (pintype "passive+no_connect"))
    )
    (net (code "56") (name "unconnected-(U200-PMBUS_ALERT-Pad19)") (class "Default")
      (node (ref "U200") (pin "19") (pinfunction "PMBUS_ALERT_19") (pintype "bidirectional+no_connect"))
    )
    (net (code "57") (name "unconnected-(U201-B2-Pad1)") (class "Default")
      (node (ref "U201") (pin "1") (pinfunction "B2_1") (pintype "input+no_connect"))
    )
  )
)
